# ife19_TS_BMS_LTC6813_Testing.net
KiCad netlist of a schematic drawn in EAGLE
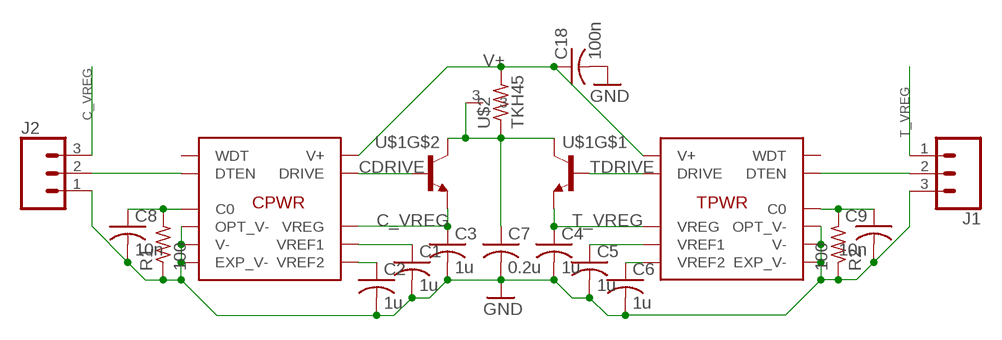
[diagram p0: schematic, sheet 1]
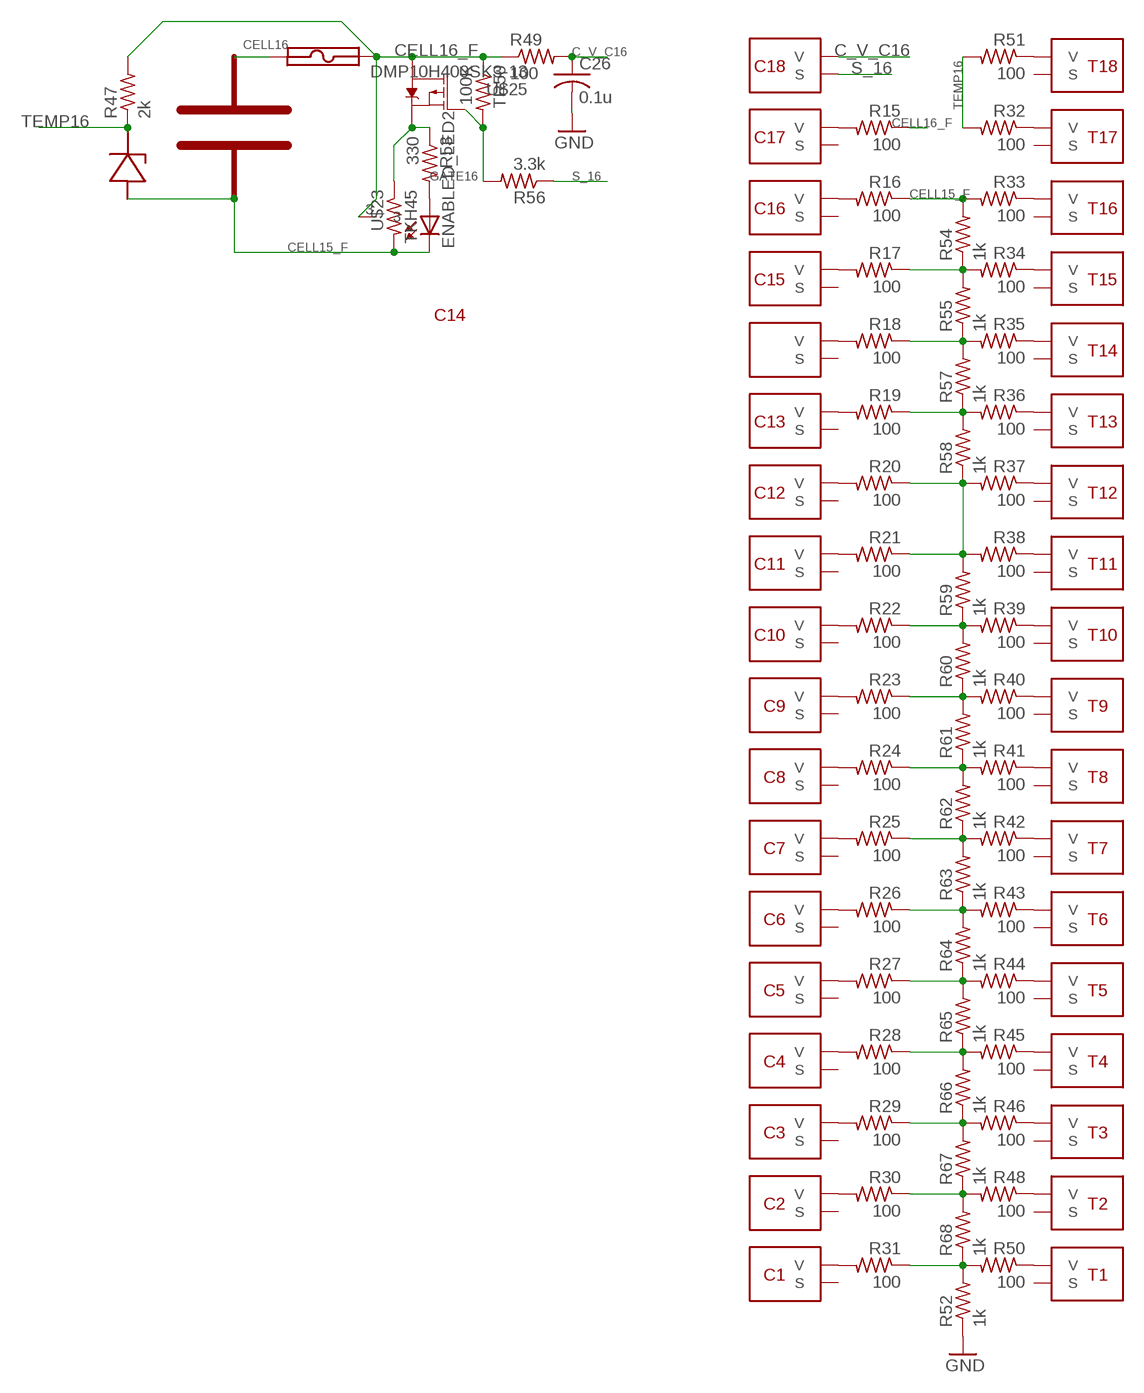
[diagram p1: schematic, sheet 2]
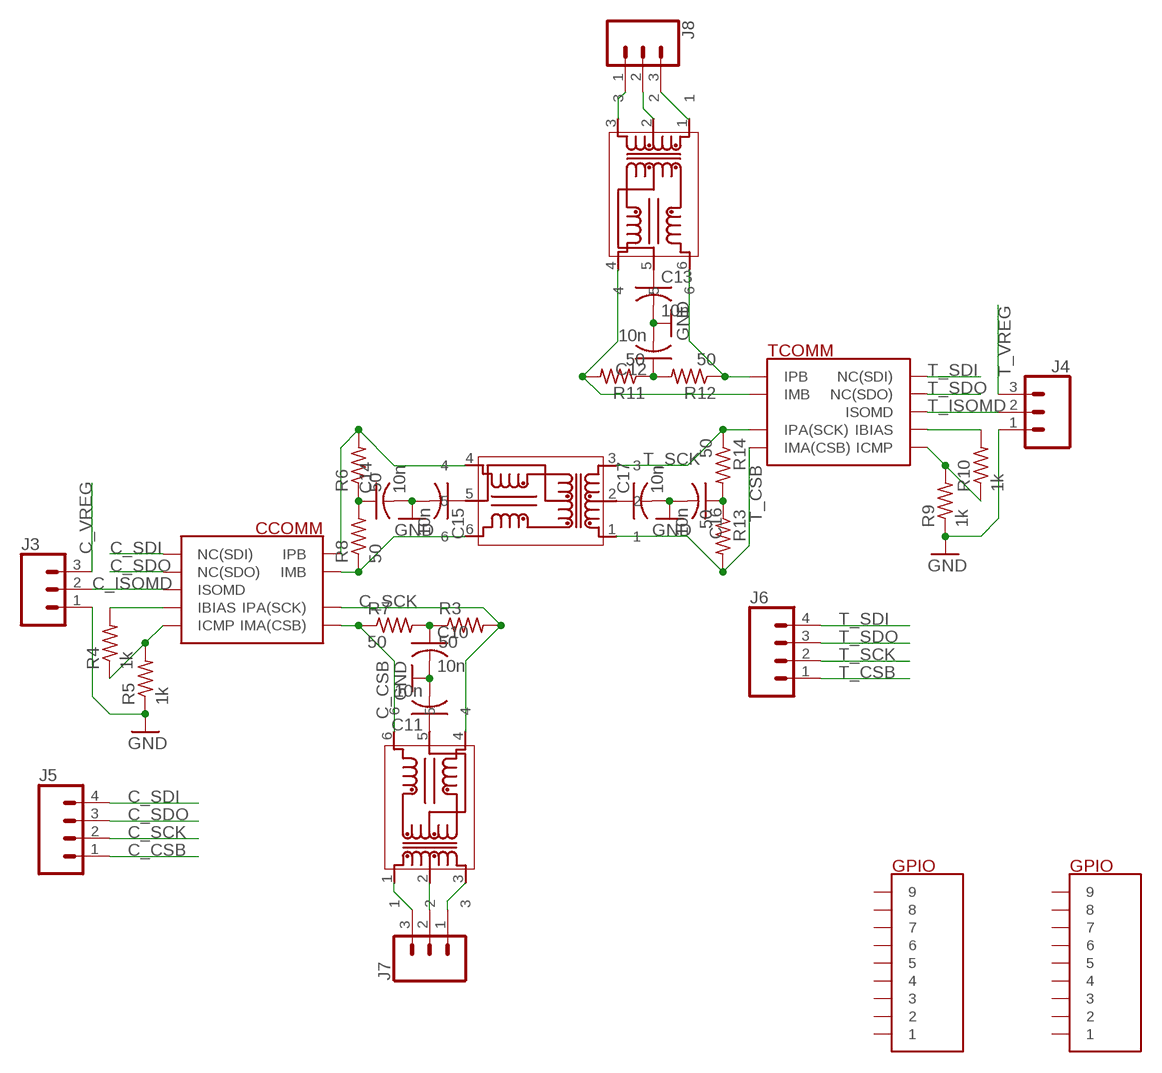
[diagram p2: schematic, sheet 3]

(export (version "E")
  (design (tool "Eeschema 10.0.6"))
  (components
    (comp (ref "C")
      (value "LTC6813-1")
      (footprint "eagle-import:HTQFP-64-EXP")
      (libsource (lib "eagle-import") (part "LTC6813-1"))
    )
    (comp (ref "C1")
      (value "1u")
      (footprint "eagle-import:C0603")
      (libsource (lib "eagle-import") (part "C-USC0603"))
    )
    (comp (ref "C2")
      (value "1u")
      (footprint "eagle-import:C0603")
      (libsource (lib "eagle-import") (part "C-USC0603"))
    )
    (comp (ref "C3")
      (value "1u")
      (footprint "eagle-import:C0603")
      (libsource (lib "eagle-import") (part "C-USC0603"))
    )
    (comp (ref "C4")
      (value "1u")
      (footprint "eagle-import:C0603")
      (libsource (lib "eagle-import") (part "C-USC0603"))
    )
    (comp (ref "C5")
      (value "1u")
      (footprint "eagle-import:C0603")
      (libsource (lib "eagle-import") (part "C-USC0603"))
    )
    (comp (ref "C6")
      (value "1u")
      (footprint "eagle-import:C0603")
      (libsource (lib "eagle-import") (part "C-USC0603"))
    )
    (comp (ref "C7")
      (value "0.2u")
      (footprint "eagle-import:C1206")
      (libsource (lib "eagle-import") (part "C-USC1206"))
    )
    (comp (ref "C8")
      (value "10n")
      (footprint "eagle-import:C0603")
      (libsource (lib "eagle-import") (part "C-USC0603"))
    )
    (comp (ref "C9")
      (value "10n")
      (footprint "eagle-import:C0603")
      (libsource (lib "eagle-import") (part "C-USC0603"))
    )
    (comp (ref "C18")
      (value "100n")
      (footprint "eagle-import:C0603")
      (libsource (lib "eagle-import") (part "C-USC0603"))
    )
    (comp (ref "J1")
      (value "CONN_03")
      (footprint "eagle-import:1X03")
      (libsource (lib "eagle-import") (part "CONN_03"))
    )
    (comp (ref "J2")
      (value "CONN_03")
      (footprint "eagle-import:1X03")
      (libsource (lib "eagle-import") (part "CONN_03"))
    )
    (comp (ref "R1")
      (value "100")
      (footprint "eagle-import:R0603")
      (libsource (lib "eagle-import") (part "R-US_R0603"))
    )
    (comp (ref "R2")
      (value "100")
      (footprint "eagle-import:R0603")
      (libsource (lib "eagle-import") (part "R-US_R0603"))
    )
    (comp (ref "T")
      (value "LTC6813-1")
      (footprint "eagle-import:HTQFP-64-EXP")
      (libsource (lib "eagle-import") (part "LTC6813-1"))
    )
    (comp (ref "U$1")
      (value "PHPT610030NK")
      (footprint "eagle-import:LFPAK56D")
      (libsource (lib "eagle-import") (part "PHPT610030NK"))
    )
    (comp (ref "U$2")
      (value "TKH45")
      (footprint "eagle-import:TO252-TKH-45")
      (libsource (lib "eagle-import") (part "TKH45"))
    )
    (comp (ref "C10")
      (value "10n")
      (footprint "eagle-import:C0603K")
      (libsource (lib "eagle-import") (part "C-USC0603K"))
    )
    (comp (ref "C11")
      (value "10n")
      (footprint "eagle-import:C0603K")
      (libsource (lib "eagle-import") (part "C-USC0603K"))
    )
    (comp (ref "C12")
      (value "10n")
      (footprint "eagle-import:C0603K")
      (libsource (lib "eagle-import") (part "C-USC0603K"))
    )
    (comp (ref "C13")
      (value "10n")
      (footprint "eagle-import:C0603K")
      (libsource (lib "eagle-import") (part "C-USC0603K"))
    )
    (comp (ref "C14")
      (value "10n")
      (footprint "eagle-import:C0603K")
      (libsource (lib "eagle-import") (part "C-USC0603K"))
    )
    (comp (ref "C15")
      (value "10n")
      (footprint "eagle-import:C0603K")
      (libsource (lib "eagle-import") (part "C-USC0603K"))
    )
    (comp (ref "C16")
      (value "10n")
      (footprint "eagle-import:C0603K")
      (libsource (lib "eagle-import") (part "C-USC0603K"))
    )
    (comp (ref "C17")
      (value "10n")
      (footprint "eagle-import:C0603K")
      (libsource (lib "eagle-import") (part "C-USC0603K"))
    )
    (comp (ref "J3")
      (value "CONN_03")
      (footprint "eagle-import:1X03")
      (libsource (lib "eagle-import") (part "CONN_03"))
    )
    (comp (ref "J4")
      (value "CONN_03")
      (footprint "eagle-import:1X03")
      (libsource (lib "eagle-import") (part "CONN_03"))
    )
    (comp (ref "J5")
      (value "CONN_04")
      (footprint "eagle-import:1X04")
      (libsource (lib "eagle-import") (part "CONN_04"))
    )
    (comp (ref "J6")
      (value "CONN_04")
      (footprint "eagle-import:1X04")
      (libsource (lib "eagle-import") (part "CONN_04"))
    )
    (comp (ref "J7")
      (value "CONN_03")
      (footprint "eagle-import:1X03")
      (libsource (lib "eagle-import") (part "CONN_03"))
    )
    (comp (ref "J8")
      (value "CONN_03")
      (footprint "eagle-import:1X03")
      (libsource (lib "eagle-import") (part "CONN_03"))
    )
    (comp (ref "R3")
      (value "50")
      (footprint "eagle-import:R0603")
      (libsource (lib "eagle-import") (part "R-US_R0603"))
    )
    (comp (ref "R4")
      (value "1k")
      (footprint "eagle-import:R0603")
      (libsource (lib "eagle-import") (part "R-US_R0603"))
    )
    (comp (ref "R5")
      (value "1k")
      (footprint "eagle-import:R0603")
      (libsource (lib "eagle-import") (part "R-US_R0603"))
    )
    (comp (ref "R6")
      (value "50")
      (footprint "eagle-import:R0603")
      (libsource (lib "eagle-import") (part "R-US_R0603"))
    )
    (comp (ref "R7")
      (value "50")
      (footprint "eagle-import:R0603")
      (libsource (lib "eagle-import") (part "R-US_R0603"))
    )
    (comp (ref "R8")
      (value "50")
      (footprint "eagle-import:R0603")
      (libsource (lib "eagle-import") (part "R-US_R0603"))
    )
    (comp (ref "R9")
      (value "1k")
      (footprint "eagle-import:R0603")
      (libsource (lib "eagle-import") (part "R-US_R0603"))
    )
    (comp (ref "R10")
      (value "1k")
      (footprint "eagle-import:R0603")
      (libsource (lib "eagle-import") (part "R-US_R0603"))
    )
    (comp (ref "R11")
      (value "50")
      (footprint "eagle-import:R0603")
      (libsource (lib "eagle-import") (part "R-US_R0603"))
    )
    (comp (ref "R12")
      (value "50")
      (footprint "eagle-import:R0603")
      (libsource (lib "eagle-import") (part "R-US_R0603"))
    )
    (comp (ref "R13")
      (value "50")
      (footprint "eagle-import:R0603")
      (libsource (lib "eagle-import") (part "R-US_R0603"))
    )
    (comp (ref "R14")
      (value "50")
      (footprint "eagle-import:R0603")
      (libsource (lib "eagle-import") (part "R-US_R0603"))
    )
    (comp (ref "U$3")
      (value "HM2108NL")
      (footprint "eagle-import:HM2108NL")
      (libsource (lib "eagle-import") (part "HM2108NL"))
    )
    (comp (ref "U$4")
      (value "HM2108NL")
      (footprint "eagle-import:HM2108NL")
      (libsource (lib "eagle-import") (part "HM2108NL"))
    )
    (comp (ref "U$5")
      (value "HM2108NL")
      (footprint "eagle-import:HM2108NL")
      (libsource (lib "eagle-import") (part "HM2108NL"))
    )
    (comp (ref "C26")
      (value "0.1u")
      (footprint "eagle-import:C0603K")
      (libsource (lib "eagle-import") (part "C-USC0603K"))
    )
    (comp (ref "ENABLED_LED2")
      (value "LEDCHIPLED_0603")
      (footprint "eagle-import:CHIPLED_0603")
      (libsource (lib "eagle-import") (part "LEDCHIPLED_0603"))
    )
    (comp (ref "R15")
      (value "100")
      (footprint "eagle-import:R0603")
      (libsource (lib "eagle-import") (part "R-US_R0603"))
    )
    (comp (ref "R16")
      (value "100")
      (footprint "eagle-import:R0603")
      (libsource (lib "eagle-import") (part "R-US_R0603"))
    )
    (comp (ref "R17")
      (value "100")
      (footprint "eagle-import:R0603")
      (libsource (lib "eagle-import") (part "R-US_R0603"))
    )
    (comp (ref "R18")
      (value "100")
      (footprint "eagle-import:R0603")
      (libsource (lib "eagle-import") (part "R-US_R0603"))
    )
    (comp (ref "R19")
      (value "100")
      (footprint "eagle-import:R0603")
      (libsource (lib "eagle-import") (part "R-US_R0603"))
    )
    (comp (ref "R20")
      (value "100")
      (footprint "eagle-import:R0603")
      (libsource (lib "eagle-import") (part "R-US_R0603"))
    )
    (comp (ref "R21")
      (value "100")
      (footprint "eagle-import:R0603")
      (libsource (lib "eagle-import") (part "R-US_R0603"))
    )
    (comp (ref "R22")
      (value "100")
      (footprint "eagle-import:R0603")
      (libsource (lib "eagle-import") (part "R-US_R0603"))
    )
    (comp (ref "R23")
      (value "100")
      (footprint "eagle-import:R0603")
      (libsource (lib "eagle-import") (part "R-US_R0603"))
    )
    (comp (ref "R24")
      (value "100")
      (footprint "eagle-import:R0603")
      (libsource (lib "eagle-import") (part "R-US_R0603"))
    )
    (comp (ref "R25")
      (value "100")
      (footprint "eagle-import:R0603")
      (libsource (lib "eagle-import") (part "R-US_R0603"))
    )
    (comp (ref "R26")
      (value "100")
      (footprint "eagle-import:R0603")
      (libsource (lib "eagle-import") (part "R-US_R0603"))
    )
    (comp (ref "R27")
      (value "100")
      (footprint "eagle-import:R0603")
      (libsource (lib "eagle-import") (part "R-US_R0603"))
    )
    (comp (ref "R28")
      (value "100")
      (footprint "eagle-import:R0603")
      (libsource (lib "eagle-import") (part "R-US_R0603"))
    )
    (comp (ref "R29")
      (value "100")
      (footprint "eagle-import:R0603")
      (libsource (lib "eagle-import") (part "R-US_R0603"))
    )
    (comp (ref "R30")
      (value "100")
      (footprint "eagle-import:R0603")
      (libsource (lib "eagle-import") (part "R-US_R0603"))
    )
    (comp (ref "R31")
      (value "100")
      (footprint "eagle-import:R0603")
      (libsource (lib "eagle-import") (part "R-US_R0603"))
    )
    (comp (ref "R32")
      (value "100")
      (footprint "eagle-import:R0603")
      (libsource (lib "eagle-import") (part "R-US_R0603"))
    )
    (comp (ref "R33")
      (value "100")
      (footprint "eagle-import:R0603")
      (libsource (lib "eagle-import") (part "R-US_R0603"))
    )
    (comp (ref "R34")
      (value "100")
      (footprint "eagle-import:R0603")
      (libsource (lib "eagle-import") (part "R-US_R0603"))
    )
    (comp (ref "R35")
      (value "100")
      (footprint "eagle-import:R0603")
      (libsource (lib "eagle-import") (part "R-US_R0603"))
    )
    (comp (ref "R36")
      (value "100")
      (footprint "eagle-import:R0603")
      (libsource (lib "eagle-import") (part "R-US_R0603"))
    )
    (comp (ref "R37")
      (value "100")
      (footprint "eagle-import:R0603")
      (libsource (lib "eagle-import") (part "R-US_R0603"))
    )
    (comp (ref "R38")
      (value "100")
      (footprint "eagle-import:R0603")
      (libsource (lib "eagle-import") (part "R-US_R0603"))
    )
    (comp (ref "R39")
      (value "100")
      (footprint "eagle-import:R0603")
      (libsource (lib "eagle-import") (part "R-US_R0603"))
    )
    (comp (ref "R40")
      (value "100")
      (footprint "eagle-import:R0603")
      (libsource (lib "eagle-import") (part "R-US_R0603"))
    )
    (comp (ref "R41")
      (value "100")
      (footprint "eagle-import:R0603")
      (libsource (lib "eagle-import") (part "R-US_R0603"))
    )
    (comp (ref "R42")
      (value "100")
      (footprint "eagle-import:R0603")
      (libsource (lib "eagle-import") (part "R-US_R0603"))
    )
    (comp (ref "R43")
      (value "100")
      (footprint "eagle-import:R0603")
      (libsource (lib "eagle-import") (part "R-US_R0603"))
    )
    (comp (ref "R44")
      (value "100")
      (footprint "eagle-import:R0603")
      (libsource (lib "eagle-import") (part "R-US_R0603"))
    )
    (comp (ref "R45")
      (value "100")
      (footprint "eagle-import:R0603")
      (libsource (lib "eagle-import") (part "R-US_R0603"))
    )
    (comp (ref "R46")
      (value "100")
      (footprint "eagle-import:R0603")
      (libsource (lib "eagle-import") (part "R-US_R0603"))
    )
    (comp (ref "R47")
      (value "2k")
      (footprint "eagle-import:R0603")
      (libsource (lib "eagle-import") (part "R-US_R0603"))
    )
    (comp (ref "R48")
      (value "100")
      (footprint "eagle-import:R0603")
      (libsource (lib "eagle-import") (part "R-US_R0603"))
    )
    (comp (ref "R49")
      (value "100")
      (footprint "eagle-import:R0603")
      (libsource (lib "eagle-import") (part "R-US_R0603"))
    )
    (comp (ref "R50")
      (value "100")
      (footprint "eagle-import:R0603")
      (libsource (lib "eagle-import") (part "R-US_R0603"))
    )
    (comp (ref "R51")
      (value "100")
      (footprint "eagle-import:R0603")
      (libsource (lib "eagle-import") (part "R-US_R0603"))
    )
    (comp (ref "R52")
      (value "1k")
      (footprint "eagle-import:R0603")
      (libsource (lib "eagle-import") (part "R-US_R0603"))
    )
    (comp (ref "R53")
      (value "330")
      (footprint "eagle-import:R0603")
      (libsource (lib "eagle-import") (part "R-US_R0603"))
    )
    (comp (ref "R54")
      (value "1k")
      (footprint "eagle-import:R0603")
      (libsource (lib "eagle-import") (part "R-US_R0603"))
    )
    (comp (ref "R55")
      (value "1k")
      (footprint "eagle-import:R0603")
      (libsource (lib "eagle-import") (part "R-US_R0603"))
    )
    (comp (ref "R56")
      (value "3.3k")
      (footprint "eagle-import:R0603")
      (libsource (lib "eagle-import") (part "R-US_R0603"))
    )
    (comp (ref "R57")
      (value "1k")
      (footprint "eagle-import:R0603")
      (libsource (lib "eagle-import") (part "R-US_R0603"))
    )
    (comp (ref "R58")
      (value "1k")
      (footprint "eagle-import:R0603")
      (libsource (lib "eagle-import") (part "R-US_R0603"))
    )
    (comp (ref "R59")
      (value "1k")
      (footprint "eagle-import:R0603")
      (libsource (lib "eagle-import") (part "R-US_R0603"))
    )
    (comp (ref "R60")
      (value "1k")
      (footprint "eagle-import:R0603")
      (libsource (lib "eagle-import") (part "R-US_R0603"))
    )
    (comp (ref "R61")
      (value "1k")
      (footprint "eagle-import:R0603")
      (libsource (lib "eagle-import") (part "R-US_R0603"))
    )
    (comp (ref "R62")
      (value "1k")
      (footprint "eagle-import:R0603")
      (libsource (lib "eagle-import") (part "R-US_R0603"))
    )
    (comp (ref "R63")
      (value "1k")
      (footprint "eagle-import:R0603")
      (libsource (lib "eagle-import") (part "R-US_R0603"))
    )
    (comp (ref "R64")
      (value "1k")
      (footprint "eagle-import:R0603")
      (libsource (lib "eagle-import") (part "R-US_R0603"))
    )
    (comp (ref "R65")
      (value "1k")
      (footprint "eagle-import:R0603")
      (libsource (lib "eagle-import") (part "R-US_R0603"))
    )
    (comp (ref "R66")
      (value "1k")
      (footprint "eagle-import:R0603")
      (libsource (lib "eagle-import") (part "R-US_R0603"))
    )
    (comp (ref "R67")
      (value "1k")
      (footprint "eagle-import:R0603")
      (libsource (lib "eagle-import") (part "R-US_R0603"))
    )
    (comp (ref "R68")
      (value "1k")
      (footprint "eagle-import:R0603")
      (libsource (lib "eagle-import") (part "R-US_R0603"))
    )
    (comp (ref "TR50")
      (value "100K")
      (footprint "eagle-import:R0603")
      (libsource (lib "eagle-import") (part "R-US_R0603"))
    )
    (comp (ref "U$6")
      (value "LI6PT")
      (footprint "eagle-import:6PT")
      (libsource (lib "eagle-import") (part "LI6PT"))
    )
    (comp (ref "U$22")
      (value "04661206")
      (footprint "eagle-import:R1206W")
      (libsource (lib "eagle-import") (part "04661206"))
    )
    (comp (ref "U$23")
      (value "TKH45")
      (footprint "eagle-import:TO252-TKH-45")
      (libsource (lib "eagle-import") (part "TKH45"))
    )
    (comp (ref "U$25")
      (value "DMP10H400SK3-13")
      (footprint "eagle-import:TO252")
      (libsource (lib "eagle-import") (part "DMP10H400SK3-13"))
    )
  )
  (nets
    (net (code "1") (name "CDRIVE") (class "Default")
      (node (ref "C") (pin "49") (pinfunction "DRIVE_49") (pintype "bidirectional"))
      (node (ref "U$1") (pin "B2") (pinfunction "B_B2") (pintype "passive"))
    )
    (net (code "2") (name "CELL15_F") (class "Default")
      (node (ref "ENABLED_LED2") (pin "C") (pinfunction "C_C") (pintype "passive"))
      (node (ref "R16") (pin "1") (pinfunction "1_1") (pintype "passive"))
      (node (ref "R33") (pin "2") (pinfunction "2_2") (pintype "passive"))
      (node (ref "R54") (pin "2") (pinfunction "2_2") (pintype "passive"))
      (node (ref "U$23") (pin "2") (pinfunction "2_2") (pintype "passive"))
      (node (ref "U$6") (pin "1") (pinfunction "TEMP-_1") (pintype "bidirectional"))
      (node (ref "U$6") (pin "CELLH-") (pinfunction "CELL-_CELLH-") (pintype "bidirectional"))
      (node (ref "U$6") (pin "CELLP-") (pinfunction "CELL-_CELLP-") (pintype "bidirectional"))
    )
    (net (code "3") (name "CELL16") (class "Default")
      (node (ref "U$22") (pin "1") (pinfunction "P$1_1") (pintype "bidirectional"))
      (node (ref "U$6") (pin "CELLH+") (pinfunction "CELL+_CELLH+") (pintype "bidirectional"))
      (node (ref "U$6") (pin "CELLP+") (pinfunction "CELL+_CELLP+") (pintype "bidirectional"))
    )
    (net (code "4") (name "CELL16_F") (class "Default")
      (node (ref "R15") (pin "1") (pinfunction "1_1") (pintype "passive"))
      (node (ref "R47") (pin "2") (pinfunction "2_2") (pintype "passive"))
      (node (ref "R49") (pin "1") (pinfunction "1_1") (pintype "passive"))
      (node (ref "TR50") (pin "1") (pinfunction "1_1") (pintype "passive"))
      (node (ref "U$22") (pin "2") (pinfunction "P$2_2") (pintype "bidirectional"))
      (node (ref "U$23") (pin "3") (pinfunction "3_3") (pintype "passive"))
      (node (ref "U$25") (pin "2") (pinfunction "D_2") (pintype "bidirectional"))
    )
    (net (code "5") (name "C_CSB") (class "Default")
      (node (ref "C") (pin "61") (pinfunction "IMA(CSB)_61") (pintype "bidirectional"))
      (node (ref "J5") (pin "1") (pinfunction "1_1") (pintype "passive"))
      (node (ref "R7") (pin "1") (pinfunction "1_1") (pintype "passive"))
      (node (ref "U$3") (pin "6") (pinfunction "6_6") (pintype "bidirectional"))
    )
    (net (code "6") (name "C_ISOMD") (class "Default")
      (node (ref "C") (pin "55") (pinfunction "ISOMD_55") (pintype "bidirectional"))
      (node (ref "J3") (pin "2") (pinfunction "2_2") (pintype "passive"))
    )
    (net (code "7") (name "C_SCK") (class "Default")
      (node (ref "C") (pin "62") (pinfunction "IPA(SCK)_62") (pintype "bidirectional"))
      (node (ref "J5") (pin "2") (pinfunction "2_2") (pintype "passive"))
      (node (ref "R3") (pin "2") (pinfunction "2_2") (pintype "passive"))
      (node (ref "U$3") (pin "4") (pinfunction "4_4") (pintype "bidirectional"))
    )
    (net (code "8") (name "C_SDI") (class "Default")
      (node (ref "C") (pin "53") (pinfunction "NC(SDI)_53") (pintype "bidirectional"))
      (node (ref "J5") (pin "4") (pinfunction "4_4") (pintype "passive"))
    )
    (net (code "9") (name "C_SDO") (class "Default")
      (node (ref "C") (pin "54") (pinfunction "NC(SDO)_54") (pintype "bidirectional"))
      (node (ref "J5") (pin "3") (pinfunction "3_3") (pintype "passive"))
    )
    (net (code "10") (name "C_VREG") (class "Default")
      (node (ref "C") (pin "48") (pinfunction "VREG_48") (pintype "bidirectional"))
      (node (ref "C3") (pin "1") (pinfunction "1_1") (pintype "passive"))
      (node (ref "J2") (pin "3") (pinfunction "3_3") (pintype "passive"))
      (node (ref "J3") (pin "3") (pinfunction "3_3") (pintype "passive"))
      (node (ref "U$1") (pin "E2") (pinfunction "E_E2") (pintype "passive"))
    )
    (net (code "11") (name "C_V_C16") (class "Default")
      (node (ref "C") (pin "2") (pinfunction "V_2") (pintype "bidirectional"))
      (node (ref "C26") (pin "1") (pinfunction "1_1") (pintype "passive"))
      (node (ref "R49") (pin "2") (pinfunction "2_2") (pintype "passive"))
    )
    (net (code "12") (name "GATE16") (class "Default")
      (node (ref "R56") (pin "2") (pinfunction "2_2") (pintype "passive"))
      (node (ref "TR50") (pin "2") (pinfunction "2_2") (pintype "passive"))
      (node (ref "U$25") (pin "1") (pinfunction "G_1") (pintype "bidirectional"))
    )
    (net (code "13") (name "GND") (class "Default")
      (node (ref "C") (pin "59") (pinfunction "V-_59") (pintype "bidirectional"))
      (node (ref "C") (pin "60") (pinfunction "OPT_V-_60") (pintype "bidirectional"))
      (node (ref "C") (pin "65") (pinfunction "EXP_V-_65") (pintype "bidirectional"))
      (node (ref "C1") (pin "2") (pinfunction "2_2") (pintype "passive"))
      (node (ref "C10") (pin "2") (pinfunction "2_2") (pintype "passive"))
      (node (ref "C11") (pin "2") (pinfunction "2_2") (pintype "passive"))
      (node (ref "C12") (pin "2") (pinfunction "2_2") (pintype "passive"))
      (node (ref "C13") (pin "2") (pinfunction "2_2") (pintype "passive"))
      (node (ref "C14") (pin "2") (pinfunction "2_2") (pintype "passive"))
      (node (ref "C15") (pin "2") (pinfunction "2_2") (pintype "passive"))
      (node (ref "C16") (pin "2") (pinfunction "2_2") (pintype "passive"))
      (node (ref "C17") (pin "2") (pinfunction "2_2") (pintype "passive"))
      (node (ref "C18") (pin "2") (pinfunction "2_2") (pintype "passive"))
      (node (ref "C2") (pin "2") (pinfunction "2_2") (pintype "passive"))
      (node (ref "C26") (pin "2") (pinfunction "2_2") (pintype "passive"))
      (node (ref "C3") (pin "2") (pinfunction "2_2") (pintype "passive"))
      (node (ref "C4") (pin "2") (pinfunction "2_2") (pintype "passive"))
      (node (ref "C5") (pin "2") (pinfunction "2_2") (pintype "passive"))
      (node (ref "C6") (pin "2") (pinfunction "2_2") (pintype "passive"))
      (node (ref "C7") (pin "2") (pinfunction "2_2") (pintype "passive"))
      (node (ref "C8") (pin "2") (pinfunction "2_2") (pintype "passive"))
      (node (ref "C9") (pin "2") (pinfunction "2_2") (pintype "passive"))
      (node (ref "J1") (pin "3") (pinfunction "3_3") (pintype "passive"))
      (node (ref "J2") (pin "1") (pinfunction "1_1") (pintype "passive"))
      (node (ref "J3") (pin "1") (pinfunction "1_1") (pintype "passive"))
      (node (ref "J4") (pin "1") (pinfunction "1_1") (pintype "passive"))
      (node (ref "R1") (pin "1") (pinfunction "1_1") (pintype "passive"))
      (node (ref "R2") (pin "1") (pinfunction "1_1") (pintype "passive"))
      (node (ref "R5") (pin "1") (pinfunction "1_1") (pintype "passive"))
      (node (ref "R52") (pin "1") (pinfunction "1_1") (pintype "passive"))
      (node (ref "R9") (pin "1") (pinfunction "1_1") (pintype "passive"))
      (node (ref "T") (pin "59") (pinfunction "V-_59") (pintype "bidirectional"))
      (node (ref "T") (pin "60") (pinfunction "OPT_V-_60") (pintype "bidirectional"))
      (node (ref "T") (pin "65") (pinfunction "EXP_V-_65") (pintype "bidirectional"))
    )
    (net (code "14") (name "Net-(C10-Pad1)") (class "Default")
      (node (ref "C10") (pin "1") (pinfunction "1_1") (pintype "passive"))
      (node (ref "R3") (pin "1") (pinfunction "1_1") (pintype "passive"))
      (node (ref "R7") (pin "2") (pinfunction "2_2") (pintype "passive"))
    )
    (net (code "15") (name "Net-(C11-Pad1)") (class "Default")
      (node (ref "C11") (pin "1") (pinfunction "1_1") (pintype "passive"))
      (node (ref "U$3") (pin "5") (pinfunction "5_5") (pintype "bidirectional"))
    )
    (net (code "16") (name "Net-(C12-Pad1)") (class "Default")
      (node (ref "C12") (pin "1") (pinfunction "1_1") (pintype "passive"))
      (node (ref "R11") (pin "1") (pinfunction "1_1") (pintype "passive"))
      (node (ref "R12") (pin "2") (pinfunction "2_2") (pintype "passive"))
    )
    (net (code "17") (name "Net-(C13-Pad1)") (class "Default")
      (node (ref "C13") (pin "1") (pinfunction "1_1") (pintype "passive"))
      (node (ref "U$4") (pin "5") (pinfunction "5_5") (pintype "bidirectional"))
    )
    (net (code "18") (name "Net-(C14-Pad1)") (class "Default")
      (node (ref "C14") (pin "1") (pinfunction "1_1") (pintype "passive"))
      (node (ref "R6") (pin "1") (pinfunction "1_1") (pintype "passive"))
      (node (ref "R8") (pin "2") (pinfunction "2_2") (pintype "passive"))
    )
    (net (code "19") (name "Net-(C15-Pad1)") (class "Default")
      (node (ref "C15") (pin "1") (pinfunction "1_1") (pintype "passive"))
      (node (ref "U$5") (pin "5") (pinfunction "5_5") (pintype "bidirectional"))
    )
    (net (code "20") (name "Net-(C16-Pad1)") (class "Default")
      (node (ref "C16") (pin "1") (pinfunction "1_1") (pintype "passive"))
      (node (ref "R13") (pin "1") (pinfunction "1_1") (pintype "passive"))
      (node (ref "R14") (pin "2") (pinfunction "2_2") (pintype "passive"))
    )
    (net (code "21") (name "Net-(C17-Pad1)") (class "Default")
      (node (ref "C17") (pin "1") (pinfunction "1_1") (pintype "passive"))
      (node (ref "U$5") (pin "2") (pinfunction "2_2") (pintype "bidirectional"))
    )
    (net (code "22") (name "Net-(CA-V)") (class "Default")
      (node (ref "C") (pin "36") (pinfunction "V_36") (pintype "bidirectional"))
      (node (ref "R31") (pin "2") (pinfunction "2_2") (pintype "passive"))
    )
    (net (code "23") (name "Net-(CB-V)") (class "Default")
      (node (ref "C") (pin "18") (pinfunction "V_18") (pintype "bidirectional"))
      (node (ref "R22") (pin "2") (pinfunction "2_2") (pintype "passive"))
    )
    (net (code "24") (name "Net-(CC-V)") (class "Default")
      (node (ref "C") (pin "16") (pinfunction "V_16") (pintype "bidirectional"))
      (node (ref "R21") (pin "2") (pinfunction "2_2") (pintype "passive"))
    )
    (net (code "25") (name "Net-(CD-V)") (class "Default")
      (node (ref "C") (pin "14") (pinfunction "V_14") (pintype "bidirectional"))
      (node (ref "R20") (pin "2") (pinfunction "2_2") (pintype "passive"))
    )
    (net (code "26") (name "Net-(CE-V)") (class "Default")
      (node (ref "C") (pin "12") (pinfunction "V_12") (pintype "bidirectional"))
      (node (ref "R19") (pin "2") (pinfunction "2_2") (pintype "passive"))
    )
    (net (code "27") (name "Net-(CF-V)") (class "Default")
      (node (ref "C") (pin "10") (pinfunction "V_10") (pintype "bidirectional"))
      (node (ref "R18") (pin "2") (pinfunction "2_2") (pintype "passive"))
    )
    (net (code "28") (name "Net-(CG-V)") (class "Default")
      (node (ref "C") (pin "8") (pinfunction "V_8") (pintype "bidirectional"))
      (node (ref "R17") (pin "2") (pinfunction "2_2") (pintype "passive"))
    )
    (net (code "29") (name "Net-(CH-V)") (class "Default")
      (node (ref "C") (pin "6") (pinfunction "V_6") (pintype "bidirectional"))
      (node (ref "R16") (pin "2") (pinfunction "2_2") (pintype "passive"))
    )
    (net (code "30") (name "Net-(CI-V)") (class "Default")
      (node (ref "C") (pin "4") (pinfunction "V_4") (pintype "bidirectional"))
      (node (ref "R15") (pin "2") (pinfunction "2_2") (pintype "passive"))
    )
    (net (code "31") (name "Net-(CK-V)") (class "Default")
      (node (ref "C") (pin "34") (pinfunction "V_34") (pintype "bidirectional"))
      (node (ref "R30") (pin "2") (pinfunction "2_2") (pintype "passive"))
    )
    (net (code "32") (name "Net-(CL-V)") (class "Default")
      (node (ref "C") (pin "32") (pinfunction "V_32") (pintype "bidirectional"))
      (node (ref "R29") (pin "2") (pinfunction "2_2") (pintype "passive"))
    )
    (net (code "33") (name "Net-(CM-V)") (class "Default")
      (node (ref "C") (pin "30") (pinfunction "V_30") (pintype "bidirectional"))
      (node (ref "R28") (pin "2") (pinfunction "2_2") (pintype "passive"))
    )
    (net (code "34") (name "Net-(CN-V)") (class "Default")
      (node (ref "C") (pin "28") (pinfunction "V_28") (pintype "bidirectional"))
      (node (ref "R27") (pin "2") (pinfunction "2_2") (pintype "passive"))
    )
    (net (code "35") (name "Net-(CO-V)") (class "Default")
      (node (ref "C") (pin "26") (pinfunction "V_26") (pintype "bidirectional"))
      (node (ref "R26") (pin "2") (pinfunction "2_2") (pintype "passive"))
    )
    (net (code "36") (name "Net-(CP-V)") (class "Default")
      (node (ref "C") (pin "24") (pinfunction "V_24") (pintype "bidirectional"))
      (node (ref "R25") (pin "2") (pinfunction "2_2") (pintype "passive"))
    )
    (net (code "37") (name "Net-(CQ-V)") (class "Default")
      (node (ref "C") (pin "22") (pinfunction "V_22") (pintype "bidirectional"))
      (node (ref "R24") (pin "2") (pinfunction "2_2") (pintype "passive"))
    )
    (net (code "38") (name "Net-(CR-V)") (class "Default")
      (node (ref "C") (pin "20") (pinfunction "V_20") (pintype "bidirectional"))
      (node (ref "R23") (pin "2") (pinfunction "2_2") (pintype "passive"))
    )
    (net (code "39") (name "Net-(CS-IBIAS)") (class "Default")
      (node (ref "C") (pin "57") (pinfunction "IBIAS_57") (pintype "bidirectional"))
      (node (ref "R4") (pin "2") (pinfunction "2_2") (pintype "passive"))
    )
    (net (code "40") (name "Net-(CS-ICMP)") (class "Default")
      (node (ref "C") (pin "58") (pinfunction "ICMP_58") (pintype "bidirectional"))
      (node (ref "R4") (pin "1") (pinfunction "1_1") (pintype "passive"))
      (node (ref "R5") (pin "2") (pinfunction "2_2") (pintype "passive"))
    )
    (net (code "41") (name "Net-(CS-IMB)") (class "Default")
      (node (ref "C") (pin "63") (pinfunction "IMB_63") (pintype "bidirectional"))
      (node (ref "R8") (pin "1") (pinfunction "1_1") (pintype "passive"))
      (node (ref "U$5") (pin "6") (pinfunction "6_6") (pintype "bidirectional"))
    )
    (net (code "42") (name "Net-(CS-IPB)") (class "Default")
      (node (ref "C") (pin "64") (pinfunction "IPB_64") (pintype "bidirectional"))
      (node (ref "R6") (pin "2") (pinfunction "2_2") (pintype "passive"))
      (node (ref "U$5") (pin "4") (pinfunction "4_4") (pintype "bidirectional"))
    )
    (net (code "43") (name "Net-(CU-C0)") (class "Default")
      (node (ref "C") (pin "38") (pinfunction "C0_38") (pintype "bidirectional"))
      (node (ref "C8") (pin "1") (pinfunction "1_1") (pintype "passive"))
      (node (ref "R1") (pin "2") (pinfunction "2_2") (pintype "passive"))
    )
    (net (code "44") (name "Net-(CU-DTEN)") (class "Default")
      (node (ref "C") (pin "52") (pinfunction "DTEN_52") (pintype "bidirectional"))
      (node (ref "J2") (pin "2") (pinfunction "2_2") (pintype "passive"))
    )
    (net (code "45") (name "Net-(CU-VREF1)") (class "Default")
      (node (ref "C") (pin "51") (pinfunction "VREF1_51") (pintype "bidirectional"))
      (node (ref "C1") (pin "1") (pinfunction "1_1") (pintype "passive"))
    )
    (net (code "46") (name "Net-(CU-VREF2)") (class "Default")
      (node (ref "C") (pin "50") (pinfunction "VREF2_50") (pintype "bidirectional"))
      (node (ref "C2") (pin "1") (pinfunction "1_1") (pintype "passive"))
    )
    (net (code "47") (name "Net-(ENABLED_LED2-PadA)") (class "Default")
      (node (ref "ENABLED_LED2") (pin "A") (pinfunction "A_A") (pintype "passive"))
      (node (ref "R53") (pin "2") (pinfunction "2_2") (pintype "passive"))
    )
    (net (code "48") (name "Net-(J7-Pad1)") (class "Default")
      (node (ref "J7") (pin "1") (pinfunction "1_1") (pintype "passive"))
      (node (ref "U$3") (pin "3") (pinfunction "3_3") (pintype "bidirectional"))
    )
    (net (code "49") (name "Net-(J7-Pad2)") (class "Default")
      (node (ref "J7") (pin "2") (pinfunction "2_2") (pintype "passive"))
      (node (ref "U$3") (pin "2") (pinfunction "2_2") (pintype "bidirectional"))
    )
    (net (code "50") (name "Net-(J7-Pad3)") (class "Default")
      (node (ref "J7") (pin "3") (pinfunction "3_3") (pintype "passive"))
      (node (ref "U$3") (pin "1") (pinfunction "1_1") (pintype "bidirectional"))
    )
    (net (code "51") (name "Net-(J8-Pad1)") (class "Default")
      (node (ref "J8") (pin "1") (pinfunction "1_1") (pintype "passive"))
      (node (ref "U$4") (pin "3") (pinfunction "3_3") (pintype "bidirectional"))
    )
    (net (code "52") (name "Net-(J8-Pad2)") (class "Default")
      (node (ref "J8") (pin "2") (pinfunction "2_2") (pintype "passive"))
      (node (ref "U$4") (pin "2") (pinfunction "2_2") (pintype "bidirectional"))
    )
    (net (code "53") (name "Net-(J8-Pad3)") (class "Default")
      (node (ref "J8") (pin "3") (pinfunction "3_3") (pintype "passive"))
      (node (ref "U$4") (pin "1") (pinfunction "1_1") (pintype "bidirectional"))
    )
    (net (code "54") (name "Net-(R17-Pad1)") (class "Default")
      (node (ref "R17") (pin "1") (pinfunction "1_1") (pintype "passive"))
      (node (ref "R34") (pin "2") (pinfunction "2_2") (pintype "passive"))
      (node (ref "R54") (pin "1") (pinfunction "1_1") (pintype "passive"))
      (node (ref "R55") (pin "2") (pinfunction "2_2") (pintype "passive"))
    )
    (net (code "55") (name "Net-(R18-Pad1)") (class "Default")
      (node (ref "R18") (pin "1") (pinfunction "1_1") (pintype "passive"))
      (node (ref "R35") (pin "2") (pinfunction "2_2") (pintype "passive"))
      (node (ref "R55") (pin "1") (pinfunction "1_1") (pintype "passive"))
      (node (ref "R57") (pin "2") (pinfunction "2_2") (pintype "passive"))
    )
    (net (code "56") (name "Net-(R19-Pad1)") (class "Default")
      (node (ref "R19") (pin "1") (pinfunction "1_1") (pintype "passive"))
      (node (ref "R36") (pin "2") (pinfunction "2_2") (pintype "passive"))
      (node (ref "R57") (pin "1") (pinfunction "1_1") (pintype "passive"))
      (node (ref "R58") (pin "2") (pinfunction "2_2") (pintype "passive"))
    )
    (net (code "57") (name "Net-(R20-Pad1)") (class "Default")
      (node (ref "R20") (pin "1") (pinfunction "1_1") (pintype "passive"))
      (node (ref "R21") (pin "1") (pinfunction "1_1") (pintype "passive"))
      (node (ref "R37") (pin "2") (pinfunction "2_2") (pintype "passive"))
      (node (ref "R38") (pin "2") (pinfunction "2_2") (pintype "passive"))
      (node (ref "R58") (pin "1") (pinfunction "1_1") (pintype "passive"))
      (node (ref "R59") (pin "2") (pinfunction "2_2") (pintype "passive"))
    )
    (net (code "58") (name "Net-(R22-Pad1)") (class "Default")
      (node (ref "R22") (pin "1") (pinfunction "1_1") (pintype "passive"))
      (node (ref "R39") (pin "2") (pinfunction "2_2") (pintype "passive"))
      (node (ref "R59") (pin "1") (pinfunction "1_1") (pintype "passive"))
      (node (ref "R60") (pin "2") (pinfunction "2_2") (pintype "passive"))
    )
    (net (code "59") (name "Net-(R23-Pad1)") (class "Default")
      (node (ref "R23") (pin "1") (pinfunction "1_1") (pintype "passive"))
      (node (ref "R40") (pin "2") (pinfunction "2_2") (pintype "passive"))
      (node (ref "R60") (pin "1") (pinfunction "1_1") (pintype "passive"))
      (node (ref "R61") (pin "2") (pinfunction "2_2") (pintype "passive"))
    )
    (net (code "60") (name "Net-(R24-Pad1)") (class "Default")
      (node (ref "R24") (pin "1") (pinfunction "1_1") (pintype "passive"))
      (node (ref "R41") (pin "2") (pinfunction "2_2") (pintype "passive"))
      (node (ref "R61") (pin "1") (pinfunction "1_1") (pintype "passive"))
      (node (ref "R62") (pin "2") (pinfunction "2_2") (pintype "passive"))
    )
    (net (code "61") (name "Net-(R25-Pad1)") (class "Default")
      (node (ref "R25") (pin "1") (pinfunction "1_1") (pintype "passive"))
      (node (ref "R42") (pin "2") (pinfunction "2_2") (pintype "passive"))
      (node (ref "R62") (pin "1") (pinfunction "1_1") (pintype "passive"))
      (node (ref "R63") (pin "2") (pinfunction "2_2") (pintype "passive"))
    )
    (net (code "62") (name "Net-(R26-Pad1)") (class "Default")
      (node (ref "R26") (pin "1") (pinfunction "1_1") (pintype "passive"))
      (node (ref "R43") (pin "2") (pinfunction "2_2") (pintype "passive"))
      (node (ref "R63") (pin "1") (pinfunction "1_1") (pintype "passive"))
      (node (ref "R64") (pin "2") (pinfunction "2_2") (pintype "passive"))
    )
    (net (code "63") (name "Net-(R27-Pad1)") (class "Default")
      (node (ref "R27") (pin "1") (pinfunction "1_1") (pintype "passive"))
      (node (ref "R44") (pin "2") (pinfunction "2_2") (pintype "passive"))
      (node (ref "R64") (pin "1") (pinfunction "1_1") (pintype "passive"))
      (node (ref "R65") (pin "2") (pinfunction "2_2") (pintype "passive"))
    )
    (net (code "64") (name "Net-(R28-Pad1)") (class "Default")
      (node (ref "R28") (pin "1") (pinfunction "1_1") (pintype "passive"))
      (node (ref "R45") (pin "2") (pinfunction "2_2") (pintype "passive"))
      (node (ref "R65") (pin "1") (pinfunction "1_1") (pintype "passive"))
      (node (ref "R66") (pin "2") (pinfunction "2_2") (pintype "passive"))
    )
    (net (code "65") (name "Net-(R29-Pad1)") (class "Default")
      (node (ref "R29") (pin "1") (pinfunction "1_1") (pintype "passive"))
      (node (ref "R46") (pin "2") (pinfunction "2_2") (pintype "passive"))
      (node (ref "R66") (pin "1") (pinfunction "1_1") (pintype "passive"))
      (node (ref "R67") (pin "2") (pinfunction "2_2") (pintype "passive"))
    )
    (net (code "66") (name "Net-(R30-Pad1)") (class "Default")
      (node (ref "R30") (pin "1") (pinfunction "1_1") (pintype "passive"))
      (node (ref "R48") (pin "2") (pinfunction "2_2") (pintype "passive"))
      (node (ref "R67") (pin "1") (pinfunction "1_1") (pintype "passive"))
      (node (ref "R68") (pin "2") (pinfunction "2_2") (pintype "passive"))
    )
    (net (code "67") (name "Net-(R31-Pad1)") (class "Default")
      (node (ref "R31") (pin "1") (pinfunction "1_1") (pintype "passive"))
      (node (ref "R50") (pin "2") (pinfunction "2_2") (pintype "passive"))
      (node (ref "R52") (pin "2") (pinfunction "2_2") (pintype "passive"))
      (node (ref "R68") (pin "1") (pinfunction "1_1") (pintype "passive"))
    )
    (net (code "68") (name "Net-(TA-V)") (class "Default")
      (node (ref "R50") (pin "1") (pinfunction "1_1") (pintype "passive"))
      (node (ref "T") (pin "36") (pinfunction "V_36") (pintype "bidirectional"))
    )
    (net (code "69") (name "Net-(TB-V)") (class "Default")
      (node (ref "R39") (pin "1") (pinfunction "1_1") (pintype "passive"))
      (node (ref "T") (pin "18") (pinfunction "V_18") (pintype "bidirectional"))
    )
    (net (code "70") (name "Net-(TC-V)") (class "Default")
      (node (ref "R38") (pin "1") (pinfunction "1_1") (pintype "passive"))
      (node (ref "T") (pin "16") (pinfunction "V_16") (pintype "bidirectional"))
    )
    (net (code "71") (name "Net-(TD-V)") (class "Default")
      (node (ref "R37") (pin "1") (pinfunction "1_1") (pintype "passive"))
      (node (ref "T") (pin "14") (pinfunction "V_14") (pintype "bidirectional"))
    )
    (net (code "72") (name "Net-(TE-V)") (class "Default")
      (node (ref "R36") (pin "1") (pinfunction "1_1") (pintype "passive"))
      (node (ref "T") (pin "12") (pinfunction "V_12") (pintype "bidirectional"))
    )
    (net (code "73") (name "Net-(TF-V)") (class "Default")
      (node (ref "R35") (pin "1") (pinfunction "1_1") (pintype "passive"))
      (node (ref "T") (pin "10") (pinfunction "V_10") (pintype "bidirectional"))
    )
    (net (code "74") (name "Net-(TG-V)") (class "Default")
      (node (ref "R34") (pin "1") (pinfunction "1_1") (pintype "passive"))
      (node (ref "T") (pin "8") (pinfunction "V_8") (pintype "bidirectional"))
    )
    (net (code "75") (name "Net-(TH-V)") (class "Default")
      (node (ref "R33") (pin "1") (pinfunction "1_1") (pintype "passive"))
      (node (ref "T") (pin "6") (pinfunction "V_6") (pintype "bidirectional"))
    )
    (net (code "76") (name "Net-(TI-V)") (class "Default")
      (node (ref "R32") (pin "1") (pinfunction "1_1") (pintype "passive"))
      (node (ref "T") (pin "4") (pinfunction "V_4") (pintype "bidirectional"))
    )
    (net (code "77") (name "Net-(TJ-V)") (class "Default")
      (node (ref "R51") (pin "1") (pinfunction "1_1") (pintype "passive"))
      (node (ref "T") (pin "2") (pinfunction "V_2") (pintype "bidirectional"))
    )
    (net (code "78") (name "Net-(TK-V)") (class "Default")
      (node (ref "R48") (pin "1") (pinfunction "1_1") (pintype "passive"))
      (node (ref "T") (pin "34") (pinfunction "V_34") (pintype "bidirectional"))
    )
    (net (code "79") (name "Net-(TL-V)") (class "Default")
      (node (ref "R46") (pin "1") (pinfunction "1_1") (pintype "passive"))
      (node (ref "T") (pin "32") (pinfunction "V_32") (pintype "bidirectional"))
    )
    (net (code "80") (name "Net-(TM-V)") (class "Default")
      (node (ref "R45") (pin "1") (pinfunction "1_1") (pintype "passive"))
      (node (ref "T") (pin "30") (pinfunction "V_30") (pintype "bidirectional"))
    )
    (net (code "81") (name "Net-(TN-V)") (class "Default")
      (node (ref "R44") (pin "1") (pinfunction "1_1") (pintype "passive"))
      (node (ref "T") (pin "28") (pinfunction "V_28") (pintype "bidirectional"))
    )
    (net (code "82") (name "Net-(TO-V)") (class "Default")
      (node (ref "R43") (pin "1") (pinfunction "1_1") (pintype "passive"))
      (node (ref "T") (pin "26") (pinfunction "V_26") (pintype "bidirectional"))
    )
    (net (code "83") (name "Net-(TP-V)") (class "Default")
      (node (ref "R42") (pin "1") (pinfunction "1_1") (pintype "passive"))
      (node (ref "T") (pin "24") (pinfunction "V_24") (pintype "bidirectional"))
    )
    (net (code "84") (name "Net-(TQ-V)") (class "Default")
      (node (ref "R41") (pin "1") (pinfunction "1_1") (pintype "passive"))
      (node (ref "T") (pin "22") (pinfunction "V_22") (pintype "bidirectional"))
    )
    (net (code "85") (name "Net-(TR-V)") (class "Default")
      (node (ref "R40") (pin "1") (pinfunction "1_1") (pintype "passive"))
      (node (ref "T") (pin "20") (pinfunction "V_20") (pintype "bidirectional"))
    )
    (net (code "86") (name "Net-(TS-IBIAS)") (class "Default")
      (node (ref "R10") (pin "2") (pinfunction "2_2") (pintype "passive"))
      (node (ref "T") (pin "57") (pinfunction "IBIAS_57") (pintype "bidirectional"))
    )
    (net (code "87") (name "Net-(TS-ICMP)") (class "Default")
      (node (ref "R10") (pin "1") (pinfunction "1_1") (pintype "passive"))
      (node (ref "R9") (pin "2") (pinfunction "2_2") (pintype "passive"))
      (node (ref "T") (pin "58") (pinfunction "ICMP_58") (pintype "bidirectional"))
    )
    (net (code "88") (name "Net-(TS-IMB)") (class "Default")
      (node (ref "R11") (pin "2") (pinfunction "2_2") (pintype "passive"))
      (node (ref "T") (pin "63") (pinfunction "IMB_63") (pintype "bidirectional"))
      (node (ref "U$4") (pin "4") (pinfunction "4_4") (pintype "bidirectional"))
    )
    (net (code "89") (name "Net-(TS-IPB)") (class "Default")
      (node (ref "R12") (pin "1") (pinfunction "1_1") (pintype "passive"))
      (node (ref "T") (pin "64") (pinfunction "IPB_64") (pintype "bidirectional"))
      (node (ref "U$4") (pin "6") (pinfunction "6_6") (pintype "bidirectional"))
    )
    (net (code "90") (name "Net-(TU-C0)") (class "Default")
      (node (ref "C9") (pin "1") (pinfunction "1_1") (pintype "passive"))
      (node (ref "R2") (pin "2") (pinfunction "2_2") (pintype "passive"))
      (node (ref "T") (pin "38") (pinfunction "C0_38") (pintype "bidirectional"))
    )
    (net (code "91") (name "Net-(TU-DTEN)") (class "Default")
      (node (ref "J1") (pin "2") (pinfunction "2_2") (pintype "passive"))
      (node (ref "T") (pin "52") (pinfunction "DTEN_52") (pintype "bidirectional"))
    )
    (net (code "92") (name "Net-(TU-VREF1)") (class "Default")
      (node (ref "C5") (pin "1") (pinfunction "1_1") (pintype "passive"))
      (node (ref "T") (pin "51") (pinfunction "VREF1_51") (pintype "bidirectional"))
    )
    (net (code "93") (name "Net-(TU-VREF2)") (class "Default")
      (node (ref "C6") (pin "1") (pinfunction "1_1") (pintype "passive"))
      (node (ref "T") (pin "50") (pinfunction "VREF2_50") (pintype "bidirectional"))
    )
    (net (code "94") (name "Net-(U$1A-C)") (class "Default")
      (node (ref "C7") (pin "1") (pinfunction "1_1") (pintype "passive"))
      (node (ref "U$1") (pin "C1") (pinfunction "C_C1") (pintype "passive"))
      (node (ref "U$1") (pin "C2") (pinfunction "C_C2") (pintype "passive"))
      (node (ref "U$2") (pin "1") (pinfunction "1_1") (pintype "passive"))
      (node (ref "U$2") (pin "3") (pinfunction "3_3") (pintype "passive"))
    )
    (net (code "95") (name "Net-(U$25-S)") (class "Default")
      (node (ref "R53") (pin "1") (pinfunction "1_1") (pintype "passive"))
      (node (ref "U$23") (pin "1") (pinfunction "1_1") (pintype "passive"))
      (node (ref "U$25") (pin "3") (pinfunction "S_3") (pintype "bidirectional"))
    )
    (net (code "96") (name "S_16") (class "Default")
      (node (ref "C") (pin "3") (pinfunction "S_3") (pintype "bidirectional"))
      (node (ref "R56") (pin "1") (pinfunction "1_1") (pintype "passive"))
    )
    (net (code "97") (name "TDRIVE") (class "Default")
      (node (ref "T") (pin "49") (pinfunction "DRIVE_49") (pintype "bidirectional"))
      (node (ref "U$1") (pin "B1") (pinfunction "B_B1") (pintype "passive"))
    )
    (net (code "98") (name "TEMP16") (class "Default")
      (node (ref "R32") (pin "2") (pinfunction "2_2") (pintype "passive"))
      (node (ref "R47") (pin "1") (pinfunction "1_1") (pintype "passive"))
      (node (ref "R51") (pin "2") (pinfunction "2_2") (pintype "passive"))
      (node (ref "U$6") (pin "2") (pinfunction "TEMP+_2") (pintype "bidirectional"))
    )
    (net (code "99") (name "T_CSB") (class "Default")
      (node (ref "J6") (pin "1") (pinfunction "1_1") (pintype "passive"))
      (node (ref "R13") (pin "2") (pinfunction "2_2") (pintype "passive"))
      (node (ref "T") (pin "61") (pinfunction "IMA(CSB)_61") (pintype "bidirectional"))
      (node (ref "U$5") (pin "1") (pinfunction "1_1") (pintype "bidirectional"))
    )
    (net (code "100") (name "T_ISOMD") (class "Default")
      (node (ref "J4") (pin "2") (pinfunction "2_2") (pintype "passive"))
      (node (ref "T") (pin "55") (pinfunction "ISOMD_55") (pintype "bidirectional"))
    )
    (net (code "101") (name "T_SCK") (class "Default")
      (node (ref "J6") (pin "2") (pinfunction "2_2") (pintype "passive"))
      (node (ref "R14") (pin "1") (pinfunction "1_1") (pintype "passive"))
      (node (ref "T") (pin "62") (pinfunction "IPA(SCK)_62") (pintype "bidirectional"))
      (node (ref "U$5") (pin "3") (pinfunction "3_3") (pintype "bidirectional"))
    )
    (net (code "102") (name "T_SDI") (class "Default")
      (node (ref "J6") (pin "4") (pinfunction "4_4") (pintype "passive"))
      (node (ref "T") (pin "53") (pinfunction "NC(SDI)_53") (pintype "bidirectional"))
    )
    (net (code "103") (name "T_SDO") (class "Default")
      (node (ref "J6") (pin "3") (pinfunction "3_3") (pintype "passive"))
      (node (ref "T") (pin "54") (pinfunction "NC(SDO)_54") (pintype "bidirectional"))
    )
    (net (code "104") (name "T_VREG") (class "Default")
      (node (ref "C4") (pin "1") (pinfunction "1_1") (pintype "passive"))
      (node (ref "J1") (pin "1") (pinfunction "1_1") (pintype "passive"))
      (node (ref "J4") (pin "3") (pinfunction "3_3") (pintype "passive"))
      (node (ref "T") (pin "48") (pinfunction "VREG_48") (pintype "bidirectional"))
      (node (ref "U$1") (pin "E1") (pinfunction "E_E1") (pintype "passive"))
    )
    (net (code "105") (name "V+") (class "Default")
      (node (ref "C") (pin "1") (pinfunction "V+_1") (pintype "bidirectional"))
      (node (ref "C18") (pin "1") (pinfunction "1_1") (pintype "passive"))
      (node (ref "T") (pin "1") (pinfunction "V+_1") (pintype "bidirectional"))
      (node (ref "U$2") (pin "2") (pinfunction "2_2") (pintype "passive"))
    )
    (net (code "106") (name "unconnected-(CA-S-Pad37)") (class "Default")
      (node (ref "C") (pin "37") (pinfunction "S_37") (pintype "bidirectional"))
    )
    (net (code "107") (name "unconnected-(CB-S-Pad19)") (class "Default")
      (node (ref "C") (pin "19") (pinfunction "S_19") (pintype "bidirectional"))
    )
    (net (code "108") (name "unconnected-(CC-S-Pad17)") (class "Default")
      (node (ref "C") (pin "17") (pinfunction "S_17") (pintype "bidirectional"))
    )
    (net (code "109") (name "unconnected-(CD-S-Pad15)") (class "Default")
      (node (ref "C") (pin "15") (pinfunction "S_15") (pintype "bidirectional"))
    )
    (net (code "110") (name "unconnected-(CE-S-Pad13)") (class "Default")
      (node (ref "C") (pin "13") (pinfunction "S_13") (pintype "bidirectional"))
    )
    (net (code "111") (name "unconnected-(CF-S-Pad11)") (class "Default")
      (node (ref "C") (pin "11") (pinfunction "S_11") (pintype "bidirectional"))
    )
    (net (code "112") (name "unconnected-(CG-S-Pad9)") (class "Default")
      (node (ref "C") (pin "9") (pinfunction "S_9") (pintype "bidirectional"))
    )
    (net (code "113") (name "unconnected-(CH-S-Pad7)") (class "Default")
      (node (ref "C") (pin "7") (pinfunction "S_7") (pintype "bidirectional"))
    )
    (net (code "114") (name "unconnected-(CI-S-Pad5)") (class "Default")
      (node (ref "C") (pin "5") (pinfunction "S_5") (pintype "bidirectional"))
    )
    (net (code "115") (name "unconnected-(CK-S-Pad35)") (class "Default")
      (node (ref "C") (pin "35") (pinfunction "S_35") (pintype "bidirectional"))
    )
    (net (code "116") (name "unconnected-(CL-S-Pad33)") (class "Default")
      (node (ref "C") (pin "33") (pinfunction "S_33") (pintype "bidirectional"))
    )
    (net (code "117") (name "unconnected-(CM-S-Pad31)") (class "Default")
      (node (ref "C") (pin "31") (pinfunction "S_31") (pintype "bidirectional"))
    )
    (net (code "118") (name "unconnected-(CN-S-Pad29)") (class "Default")
      (node (ref "C") (pin "29") (pinfunction "S_29") (pintype "bidirectional"))
    )
    (net (code "119") (name "unconnected-(CO-S-Pad27)") (class "Default")
      (node (ref "C") (pin "27") (pinfunction "S_27") (pintype "bidirectional"))
    )
    (net (code "120") (name "unconnected-(CP-S-Pad25)") (class "Default")
      (node (ref "C") (pin "25") (pinfunction "S_25") (pintype "bidirectional"))
    )
    (net (code "121") (name "unconnected-(CQ-S-Pad23)") (class "Default")
      (node (ref "C") (pin "23") (pinfunction "S_23") (pintype "bidirectional"))
    )
    (net (code "122") (name "unconnected-(CR-S-Pad21)") (class "Default")
      (node (ref "C") (pin "21") (pinfunction "S_21") (pintype "bidirectional"))
    )
    (net (code "123") (name "unconnected-(CT-1-Pad39)") (class "Default")
      (node (ref "C") (pin "39") (pinfunction "1_39") (pintype "bidirectional"))
    )
    (net (code "124") (name "unconnected-(CT-2-Pad40)") (class "Default")
      (node (ref "C") (pin "40") (pinfunction "2_40") (pintype "bidirectional"))
    )
    (net (code "125") (name "unconnected-(CT-3-Pad41)") (class "Default")
      (node (ref "C") (pin "41") (pinfunction "3_41") (pintype "bidirectional"))
    )
    (net (code "126") (name "unconnected-(CT-4-Pad42)") (class "Default")
      (node (ref "C") (pin "42") (pinfunction "4_42") (pintype "bidirectional"))
    )
    (net (code "127") (name "unconnected-(CT-5-Pad43)") (class "Default")
      (node (ref "C") (pin "43") (pinfunction "5_43") (pintype "bidirectional"))
    )
    (net (code "128") (name "unconnected-(CT-6-Pad44)") (class "Default")
      (node (ref "C") (pin "44") (pinfunction "6_44") (pintype "bidirectional"))
    )
    (net (code "129") (name "unconnected-(CT-7-Pad45)") (class "Default")
      (node (ref "C") (pin "45") (pinfunction "7_45") (pintype "bidirectional"))
    )
    (net (code "130") (name "unconnected-(CT-8-Pad46)") (class "Default")
      (node (ref "C") (pin "46") (pinfunction "8_46") (pintype "bidirectional"))
    )
    (net (code "131") (name "unconnected-(CT-9-Pad47)") (class "Default")
      (node (ref "C") (pin "47") (pinfunction "9_47") (pintype "bidirectional"))
    )
    (net (code "132") (name "unconnected-(CU-WDT-Pad56)") (class "Default")
      (node (ref "C") (pin "56") (pinfunction "WDT_56") (pintype "bidirectional"))
    )
    (net (code "133") (name "unconnected-(TA-S-Pad37)") (class "Default")
      (node (ref "T") (pin "37") (pinfunction "S_37") (pintype "bidirectional"))
    )
    (net (code "134") (name "unconnected-(TB-S-Pad19)") (class "Default")
      (node (ref "T") (pin "19") (pinfunction "S_19") (pintype "bidirectional"))
    )
    (net (code "135") (name "unconnected-(TC-S-Pad17)") (class "Default")
      (node (ref "T") (pin "17") (pinfunction "S_17") (pintype "bidirectional"))
    )
    (net (code "136") (name "unconnected-(TD-S-Pad15)") (class "Default")
      (node (ref "T") (pin "15") (pinfunction "S_15") (pintype "bidirectional"))
    )
    (net (code "137") (name "unconnected-(TE-S-Pad13)") (class "Default")
      (node (ref "T") (pin "13") (pinfunction "S_13") (pintype "bidirectional"))
    )
    (net (code "138") (name "unconnected-(TF-S-Pad11)") (class "Default")
      (node (ref "T") (pin "11") (pinfunction "S_11") (pintype "bidirectional"))
    )
    (net (code "139") (name "unconnected-(TG-S-Pad9)") (class "Default")
      (node (ref "T") (pin "9") (pinfunction "S_9") (pintype "bidirectional"))
    )
    (net (code "140") (name "unconnected-(TH-S-Pad7)") (class "Default")
      (node (ref "T") (pin "7") (pinfunction "S_7") (pintype "bidirectional"))
    )
    (net (code "141") (name "unconnected-(TI-S-Pad5)") (class "Default")
      (node (ref "T") (pin "5") (pinfunction "S_5") (pintype "bidirectional"))
    )
    (net (code "142") (name "unconnected-(TJ-S-Pad3)") (class "Default")
      (node (ref "T") (pin "3") (pinfunction "S_3") (pintype "bidirectional"))
    )
    (net (code "143") (name "unconnected-(TK-S-Pad35)") (class "Default")
      (node (ref "T") (pin "35") (pinfunction "S_35") (pintype "bidirectional"))
    )
    (net (code "144") (name "unconnected-(TL-S-Pad33)") (class "Default")
      (node (ref "T") (pin "33") (pinfunction "S_33") (pintype "bidirectional"))
    )
    (net (code "145") (name "unconnected-(TM-S-Pad31)") (class "Default")
      (node (ref "T") (pin "31") (pinfunction "S_31") (pintype "bidirectional"))
    )
    (net (code "146") (name "unconnected-(TN-S-Pad29)") (class "Default")
      (node (ref "T") (pin "29") (pinfunction "S_29") (pintype "bidirectional"))
    )
    (net (code "147") (name "unconnected-(TO-S-Pad27)") (class "Default")
      (node (ref "T") (pin "27") (pinfunction "S_27") (pintype "bidirectional"))
    )
    (net (code "148") (name "unconnected-(TP-S-Pad25)") (class "Default")
      (node (ref "T") (pin "25") (pinfunction "S_25") (pintype "bidirectional"))
    )
    (net (code "149") (name "unconnected-(TQ-S-Pad23)") (class "Default")
      (node (ref "T") (pin "23") (pinfunction "S_23") (pintype "bidirectional"))
    )
    (net (code "150") (name "unconnected-(TR-S-Pad21)") (class "Default")
      (node (ref "T") (pin "21") (pinfunction "S_21") (pintype "bidirectional"))
    )
    (net (code "151") (name "unconnected-(TT-1-Pad39)") (class "Default")
      (node (ref "T") (pin "39") (pinfunction "1_39") (pintype "bidirectional"))
    )
    (net (code "152") (name "unconnected-(TT-2-Pad40)") (class "Default")
      (node (ref "T") (pin "40") (pinfunction "2_40") (pintype "bidirectional"))
    )
    (net (code "153") (name "unconnected-(TT-3-Pad41)") (class "Default")
      (node (ref "T") (pin "41") (pinfunction "3_41") (pintype "bidirectional"))
    )
    (net (code "154") (name "unconnected-(TT-4-Pad42)") (class "Default")
      (node (ref "T") (pin "42") (pinfunction "4_42") (pintype "bidirectional"))
    )
    (net (code "155") (name "unconnected-(TT-5-Pad43)") (class "Default")
      (node (ref "T") (pin "43") (pinfunction "5_43") (pintype "bidirectional"))
    )
    (net (code "156") (name "unconnected-(TT-6-Pad44)") (class "Default")
      (node (ref "T") (pin "44") (pinfunction "6_44") (pintype "bidirectional"))
    )
    (net (code "157") (name "unconnected-(TT-7-Pad45)") (class "Default")
      (node (ref "T") (pin "45") (pinfunction "7_45") (pintype "bidirectional"))
    )
    (net (code "158") (name "unconnected-(TT-8-Pad46)") (class "Default")
      (node (ref "T") (pin "46") (pinfunction "8_46") (pintype "bidirectional"))
    )
    (net (code "159") (name "unconnected-(TT-9-Pad47)") (class "Default")
      (node (ref "T") (pin "47") (pinfunction "9_47") (pintype "bidirectional"))
    )
    (net (code "160") (name "unconnected-(TU-WDT-Pad56)") (class "Default")
      (node (ref "T") (pin "56") (pinfunction "WDT_56") (pintype "bidirectional"))
    )
  )
)
